# MiscBoard_Switching.net
KiCad netlist of a schematic drawn in Altium Designer
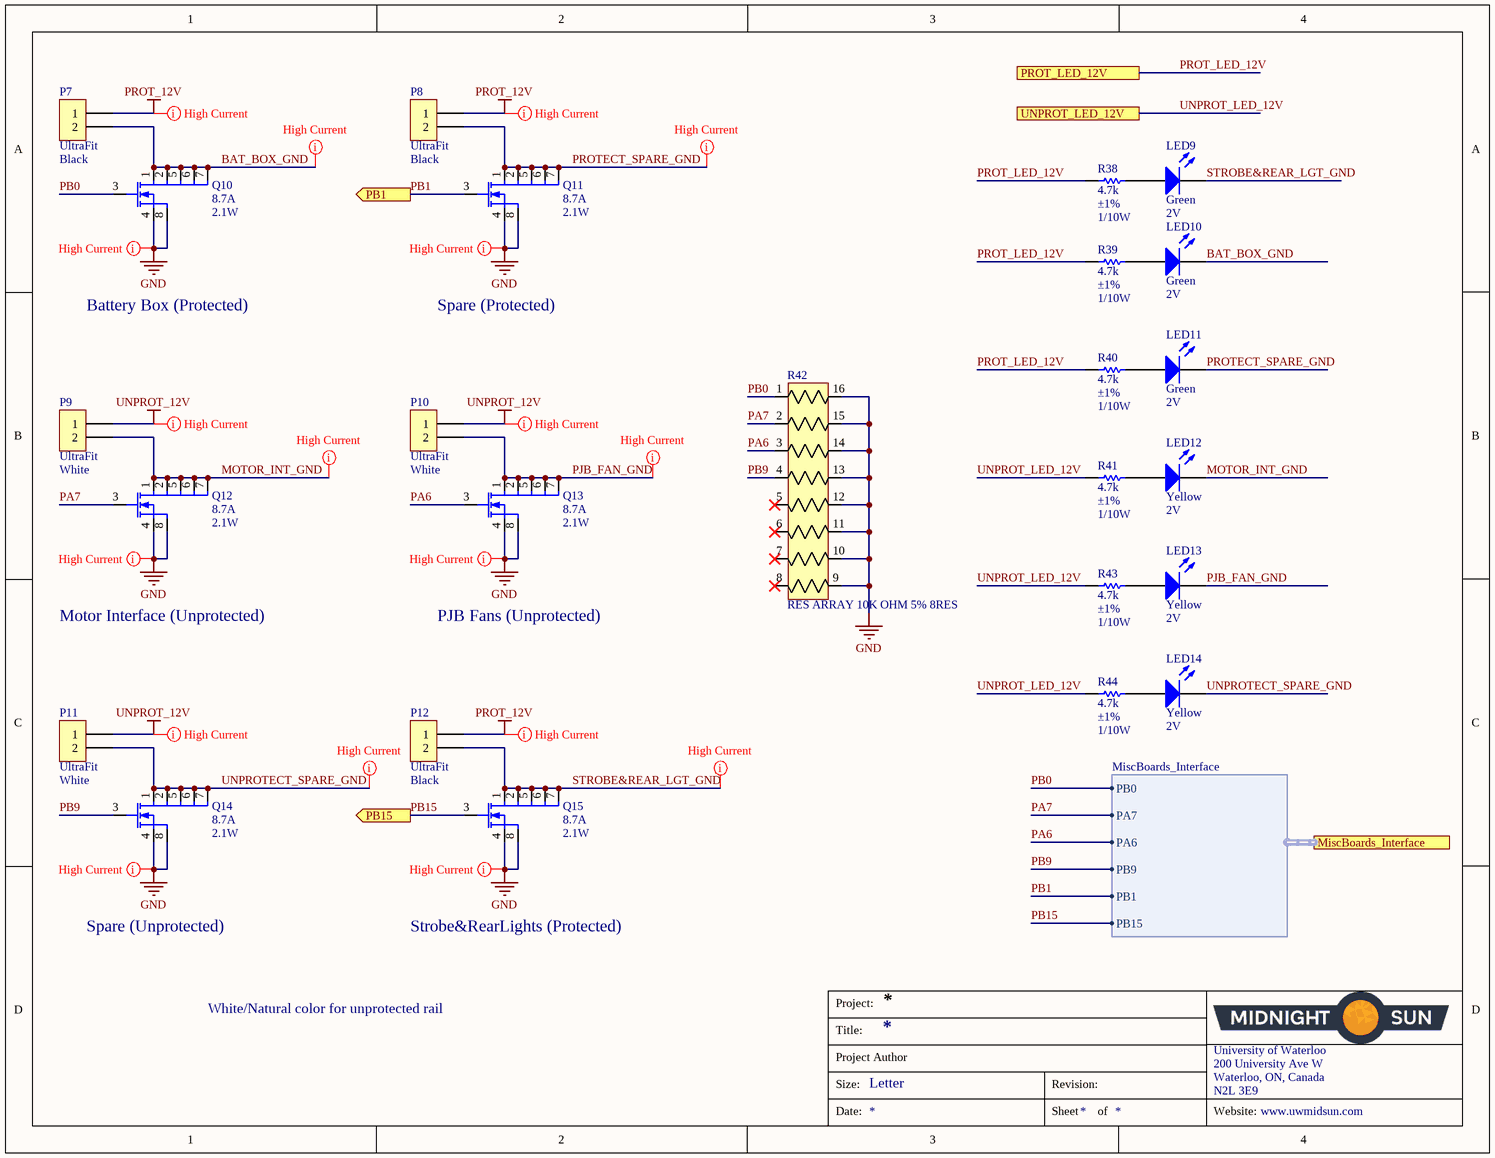
[diagram p0: MiscBoard_Switching.SchDoc]

(export (version "E")
  (design (tool "Eeschema 10.0.6"))
  (components
    (comp (ref "LED9")
      (value "LED GREEN CLEAR 2V 0603")
      (footprint "LED_0603")
      (description "Green 572nm LED Indication - Discrete 2V 0603 (1608 Metric)")
      (fields
        (field (name "COLOR") "Green")
        (field (name "VOLTAGE - FORWARD (VF) (TYP)") "2V")
        (field (name "MANUFACTURER") "Wurth Electronics Inc.")
        (field (name "MANUFACTURER PART NUMBER") "150060VS75000")
      )
      (libsource (lib "Schematic Diagrams") (part "LED GREEN CLEAR 2V 0603"))
    )
    (comp (ref "LED10")
      (value "LED GREEN CLEAR 2V 0603")
      (footprint "LED_0603")
      (description "Green 572nm LED Indication - Discrete 2V 0603 (1608 Metric)")
      (fields
        (field (name "COLOR") "Green")
        (field (name "VOLTAGE - FORWARD (VF) (TYP)") "2V")
        (field (name "MANUFACTURER") "Wurth Electronics Inc.")
        (field (name "MANUFACTURER PART NUMBER") "150060VS75000")
      )
      (libsource (lib "Schematic Diagrams") (part "LED GREEN CLEAR 2V 0603"))
    )
    (comp (ref "LED11")
      (value "LED GREEN CLEAR 2V 0603")
      (footprint "LED_0603")
      (description "Green 572nm LED Indication - Discrete 2V 0603 (1608 Metric)")
      (fields
        (field (name "COLOR") "Green")
        (field (name "VOLTAGE - FORWARD (VF) (TYP)") "2V")
        (field (name "MANUFACTURER") "Wurth Electronics Inc.")
        (field (name "MANUFACTURER PART NUMBER") "150060VS75000")
      )
      (libsource (lib "Schematic Diagrams") (part "LED GREEN CLEAR 2V 0603"))
    )
    (comp (ref "LED12")
      (value "LED YELLOW CLEAR 2.1V 0603")
      (footprint "LED_0603")
      (description "Yellow 590nm LED Indication - Discrete 2V 0603 (1608 Metric)")
      (fields
        (field (name "VOLTAGE - FORWARD (VF) (TYP)") "2V")
        (field (name "MANUFACTURER") "Wurth Electronics Inc.")
        (field (name "MANUFACTURER PART NUMBER") "150060YS75000")
      )
      (libsource (lib "Schematic Diagrams") (part "LED YELLOW CLEAR 2.1V 0603"))
    )
    (comp (ref "LED13")
      (value "LED YELLOW CLEAR 2.1V 0603")
      (footprint "LED_0603")
      (description "Yellow 590nm LED Indication - Discrete 2V 0603 (1608 Metric)")
      (fields
        (field (name "VOLTAGE - FORWARD (VF) (TYP)") "2V")
        (field (name "MANUFACTURER") "Wurth Electronics Inc.")
        (field (name "MANUFACTURER PART NUMBER") "150060YS75000")
      )
      (libsource (lib "Schematic Diagrams") (part "LED YELLOW CLEAR 2.1V 0603"))
    )
    (comp (ref "LED14")
      (value "LED YELLOW CLEAR 2.1V 0603")
      (footprint "LED_0603")
      (description "Yellow 590nm LED Indication - Discrete 2V 0603 (1608 Metric)")
      (fields
        (field (name "VOLTAGE - FORWARD (VF) (TYP)") "2V")
        (field (name "MANUFACTURER") "Wurth Electronics Inc.")
        (field (name "MANUFACTURER PART NUMBER") "150060YS75000")
      )
      (libsource (lib "Schematic Diagrams") (part "LED YELLOW CLEAR 2.1V 0603"))
    )
    (comp (ref "P7")
      (value "CONN 2POS ULTRA-FIT 0.138\"")
      (footprint "CONN, 2POS ULTRA-FIT")
      (description "2 Positions Header, Shrouded Connector 0.138\" (3.50mm) Through Hole Gold")
      (fields
        (field (name "INSULATION COLOR") "Black")
        (field (name "SERIES") "UltraFit")
        (field (name "VOLTAGE") "400V")
      )
      (libsource (lib "Schematic Diagrams") (part "CONN 2POS ULTRA-FIT 0.138{dblquote}"))
    )
    (comp (ref "P8")
      (value "CONN 2POS ULTRA-FIT 0.138\"")
      (footprint "CONN, 2POS ULTRA-FIT")
      (description "2 Positions Header, Shrouded Connector 0.138\" (3.50mm) Through Hole Gold")
      (fields
        (field (name "INSULATION COLOR") "Black")
        (field (name "SERIES") "UltraFit")
        (field (name "VOLTAGE") "400V")
      )
      (libsource (lib "Schematic Diagrams") (part "CONN 2POS ULTRA-FIT 0.138{dblquote}"))
    )
    (comp (ref "P9")
      (value "CONN 2POS ULTRA-FIT NATURAL COLOR 0.138\"")
      (footprint "CONN, 2POS ULTRA-FIT - NATURAL COLOR")
      (description "2 Positions Header, Shrouded Connector 0.138\" (3.50mm) Through Hole")
      (fields
        (field (name "SERIES") "UltraFit")
        (field (name "COLOR") "White")
        (field (name "VOLTAGE") "400V")
      )
      (libsource (lib "Schematic Diagrams") (part "CONN 2POS ULTRA-FIT NATURAL COLOR 0.138{dblquote}"))
    )
    (comp (ref "P10")
      (value "CONN 2POS ULTRA-FIT NATURAL COLOR 0.138\"")
      (footprint "CONN, 2POS ULTRA-FIT - NATURAL COLOR")
      (description "2 Positions Header, Shrouded Connector 0.138\" (3.50mm) Through Hole")
      (fields
        (field (name "SERIES") "UltraFit")
        (field (name "COLOR") "White")
        (field (name "VOLTAGE") "400V")
      )
      (libsource (lib "Schematic Diagrams") (part "CONN 2POS ULTRA-FIT NATURAL COLOR 0.138{dblquote}"))
    )
    (comp (ref "P11")
      (value "CONN 2POS ULTRA-FIT NATURAL COLOR 0.138\"")
      (footprint "CONN, 2POS ULTRA-FIT - NATURAL COLOR")
      (description "2 Positions Header, Shrouded Connector 0.138\" (3.50mm) Through Hole")
      (fields
        (field (name "SERIES") "UltraFit")
        (field (name "COLOR") "White")
        (field (name "VOLTAGE") "400V")
      )
      (libsource (lib "Schematic Diagrams") (part "CONN 2POS ULTRA-FIT NATURAL COLOR 0.138{dblquote}"))
    )
    (comp (ref "P12")
      (value "CONN 2POS ULTRA-FIT 0.138\"")
      (footprint "CONN, 2POS ULTRA-FIT")
      (description "2 Positions Header, Shrouded Connector 0.138\" (3.50mm) Through Hole Gold")
      (fields
        (field (name "INSULATION COLOR") "Black")
        (field (name "SERIES") "UltraFit")
        (field (name "VOLTAGE") "400V")
      )
      (libsource (lib "Schematic Diagrams") (part "CONN 2POS ULTRA-FIT 0.138{dblquote}"))
    )
    (comp (ref "Q10")
      (value "MOSFET N-CH 30V 8.7A 2.1W 6-PQFN (2x2)")
      (footprint "MOSFET N-CH 30V 12A 2mmx2mm PQFN")
      (fields
        (field (name "CURRENT - CONTINUOUS DRAIN (ID) @ 25°C") "8.7A")
        (field (name "POWER DISSIPATION (MAX)") "2.1W")
      )
      (libsource (lib "Schematic Diagrams") (part "MOSFET N-CH 30V 8.7A 2.1W 6-PQFN (2x2)"))
    )
    (comp (ref "Q11")
      (value "MOSFET N-CH 30V 8.7A 2.1W 6-PQFN (2x2)")
      (footprint "MOSFET N-CH 30V 12A 2mmx2mm PQFN")
      (fields
        (field (name "CURRENT - CONTINUOUS DRAIN (ID) @ 25°C") "8.7A")
        (field (name "POWER DISSIPATION (MAX)") "2.1W")
      )
      (libsource (lib "Schematic Diagrams") (part "MOSFET N-CH 30V 8.7A 2.1W 6-PQFN (2x2)"))
    )
    (comp (ref "Q12")
      (value "MOSFET N-CH 30V 8.7A 2.1W 6-PQFN (2x2)")
      (footprint "MOSFET N-CH 30V 12A 2mmx2mm PQFN")
      (fields
        (field (name "CURRENT - CONTINUOUS DRAIN (ID) @ 25°C") "8.7A")
        (field (name "POWER DISSIPATION (MAX)") "2.1W")
      )
      (libsource (lib "Schematic Diagrams") (part "MOSFET N-CH 30V 8.7A 2.1W 6-PQFN (2x2)"))
    )
    (comp (ref "Q13")
      (value "MOSFET N-CH 30V 8.7A 2.1W 6-PQFN (2x2)")
      (footprint "MOSFET N-CH 30V 12A 2mmx2mm PQFN")
      (fields
        (field (name "CURRENT - CONTINUOUS DRAIN (ID) @ 25°C") "8.7A")
        (field (name "POWER DISSIPATION (MAX)") "2.1W")
      )
      (libsource (lib "Schematic Diagrams") (part "MOSFET N-CH 30V 8.7A 2.1W 6-PQFN (2x2)"))
    )
    (comp (ref "Q14")
      (value "MOSFET N-CH 30V 8.7A 2.1W 6-PQFN (2x2)")
      (footprint "MOSFET N-CH 30V 12A 2mmx2mm PQFN")
      (fields
        (field (name "CURRENT - CONTINUOUS DRAIN (ID) @ 25°C") "8.7A")
        (field (name "POWER DISSIPATION (MAX)") "2.1W")
      )
      (libsource (lib "Schematic Diagrams") (part "MOSFET N-CH 30V 8.7A 2.1W 6-PQFN (2x2)"))
    )
    (comp (ref "Q15")
      (value "MOSFET N-CH 30V 8.7A 2.1W 6-PQFN (2x2)")
      (footprint "MOSFET N-CH 30V 12A 2mmx2mm PQFN")
      (fields
        (field (name "CURRENT - CONTINUOUS DRAIN (ID) @ 25°C") "8.7A")
        (field (name "POWER DISSIPATION (MAX)") "2.1W")
      )
      (libsource (lib "Schematic Diagrams") (part "MOSFET N-CH 30V 8.7A 2.1W 6-PQFN (2x2)"))
    )
    (comp (ref "R38")
      (value "RES 4.7K OHM 1% 1/10W 0603")
      (footprint "RES, 0603")
      (description "4.7k Ohm ±1% 0.1W, 1/10W Chip Resistor 0603 (1608 Metric) Moisture Resistant Thick Film")
      (fields
        (field (name "RESISTANCE (OHMS)") "4.7k")
        (field (name "TOLERANCE") "±1%")
        (field (name "POWER (WATTS)") "1/10W")
      )
      (libsource (lib "Schematic Diagrams") (part "RES 4.7K OHM 1% 1/10W 0603"))
    )
    (comp (ref "R39")
      (value "RES 4.7K OHM 1% 1/10W 0603")
      (footprint "RES, 0603")
      (description "4.7k Ohm ±1% 0.1W, 1/10W Chip Resistor 0603 (1608 Metric) Moisture Resistant Thick Film")
      (fields
        (field (name "RESISTANCE (OHMS)") "4.7k")
        (field (name "TOLERANCE") "±1%")
        (field (name "POWER (WATTS)") "1/10W")
      )
      (libsource (lib "Schematic Diagrams") (part "RES 4.7K OHM 1% 1/10W 0603"))
    )
    (comp (ref "R40")
      (value "RES 4.7K OHM 1% 1/10W 0603")
      (footprint "RES, 0603")
      (description "4.7k Ohm ±1% 0.1W, 1/10W Chip Resistor 0603 (1608 Metric) Moisture Resistant Thick Film")
      (fields
        (field (name "RESISTANCE (OHMS)") "4.7k")
        (field (name "TOLERANCE") "±1%")
        (field (name "POWER (WATTS)") "1/10W")
      )
      (libsource (lib "Schematic Diagrams") (part "RES 4.7K OHM 1% 1/10W 0603"))
    )
    (comp (ref "R41")
      (value "RES 4.7K OHM 1% 1/10W 0603")
      (footprint "RES, 0603")
      (description "4.7k Ohm ±1% 0.1W, 1/10W Chip Resistor 0603 (1608 Metric) Moisture Resistant Thick Film")
      (fields
        (field (name "RESISTANCE (OHMS)") "4.7k")
        (field (name "TOLERANCE") "±1%")
        (field (name "POWER (WATTS)") "1/10W")
      )
      (libsource (lib "Schematic Diagrams") (part "RES 4.7K OHM 1% 1/10W 0603"))
    )
    (comp (ref "R42")
      (value "RES ARRAY 10K OHM 5% 8RES")
      (footprint "RES ARRAY, 8 POS 1506")
      (description "RES ARRAY SMD 10K 5% 62.5mW 1506")
      (fields
        (field (name "MANUFACTURER_PART_NUMBER") "EXB-2HV103JV")
        (field (name "MANUFACTURER") "Panasonic Electronic Components")
        (field (name "COPYRIGHT") "Copyright (C) 2015 Accelerated Designs. All rights reserved")
      )
      (libsource (lib "Schematic Diagrams") (part "RES ARRAY 10K OHM 5% 8RES EXB-2HV103JV"))
    )
    (comp (ref "R43")
      (value "RES 4.7K OHM 1% 1/10W 0603")
      (footprint "RES, 0603")
      (description "4.7k Ohm ±1% 0.1W, 1/10W Chip Resistor 0603 (1608 Metric) Moisture Resistant Thick Film")
      (fields
        (field (name "RESISTANCE (OHMS)") "4.7k")
        (field (name "TOLERANCE") "±1%")
        (field (name "POWER (WATTS)") "1/10W")
      )
      (libsource (lib "Schematic Diagrams") (part "RES 4.7K OHM 1% 1/10W 0603"))
    )
    (comp (ref "R44")
      (value "RES 4.7K OHM 1% 1/10W 0603")
      (footprint "RES, 0603")
      (description "4.7k Ohm ±1% 0.1W, 1/10W Chip Resistor 0603 (1608 Metric) Moisture Resistant Thick Film")
      (fields
        (field (name "RESISTANCE (OHMS)") "4.7k")
        (field (name "TOLERANCE") "±1%")
        (field (name "POWER (WATTS)") "1/10W")
      )
      (libsource (lib "Schematic Diagrams") (part "RES 4.7K OHM 1% 1/10W 0603"))
    )
  )
  (nets
    (net (code "2") (name "/BAT_BOX_GND") (class "Default")
      (node (ref "LED10") (pin "2") (pinfunction "K_2") (pintype "passive"))
      (node (ref "P7") (pin "2") (pinfunction "2_2") (pintype "passive"))
      (node (ref "Q10") (pin "1") (pinfunction "D_1") (pintype "passive"))
      (node (ref "Q10") (pin "2") (pinfunction "D_2") (pintype "passive"))
      (node (ref "Q10") (pin "5") (pinfunction "D_5") (pintype "passive"))
      (node (ref "Q10") (pin "6") (pinfunction "D_6") (pintype "passive"))
      (node (ref "Q10") (pin "7") (pinfunction "D_7") (pintype "passive"))
    )
    (net (code "3") (name "/MOTOR_INT_GND") (class "Default")
      (node (ref "LED12") (pin "2") (pinfunction "K_2") (pintype "passive"))
      (node (ref "P9") (pin "2") (pinfunction "2_2") (pintype "passive"))
      (node (ref "Q12") (pin "1") (pinfunction "D_1") (pintype "passive"))
      (node (ref "Q12") (pin "2") (pinfunction "D_2") (pintype "passive"))
      (node (ref "Q12") (pin "5") (pinfunction "D_5") (pintype "passive"))
      (node (ref "Q12") (pin "6") (pinfunction "D_6") (pintype "passive"))
      (node (ref "Q12") (pin "7") (pinfunction "D_7") (pintype "passive"))
    )
    (net (code "4") (name "/PA6") (class "Default")
      (node (ref "Q13") (pin "3") (pinfunction "G_3") (pintype "passive"))
      (node (ref "R42") (pin "3") (pinfunction "3_3") (pintype "passive"))
    )
    (net (code "5") (name "/PA7") (class "Default")
      (node (ref "Q12") (pin "3") (pinfunction "G_3") (pintype "passive"))
      (node (ref "R42") (pin "2") (pinfunction "2_2") (pintype "passive"))
    )
    (net (code "6") (name "/PB0") (class "Default")
      (node (ref "Q10") (pin "3") (pinfunction "G_3") (pintype "passive"))
      (node (ref "R42") (pin "1") (pinfunction "1_1") (pintype "passive"))
    )
    (net (code "7") (name "/PB1") (class "Default")
      (node (ref "Q11") (pin "3") (pinfunction "G_3") (pintype "passive"))
    )
    (net (code "8") (name "/PB9") (class "Default")
      (node (ref "Q14") (pin "3") (pinfunction "G_3") (pintype "passive"))
      (node (ref "R42") (pin "4") (pinfunction "4_4") (pintype "passive"))
    )
    (net (code "9") (name "/PB15") (class "Default")
      (node (ref "Q15") (pin "3") (pinfunction "G_3") (pintype "passive"))
    )
    (net (code "10") (name "/PJB_FAN_GND") (class "Default")
      (node (ref "LED13") (pin "2") (pinfunction "K_2") (pintype "passive"))
      (node (ref "P10") (pin "2") (pinfunction "2_2") (pintype "passive"))
      (node (ref "Q13") (pin "1") (pinfunction "D_1") (pintype "passive"))
      (node (ref "Q13") (pin "2") (pinfunction "D_2") (pintype "passive"))
      (node (ref "Q13") (pin "5") (pinfunction "D_5") (pintype "passive"))
      (node (ref "Q13") (pin "6") (pinfunction "D_6") (pintype "passive"))
      (node (ref "Q13") (pin "7") (pinfunction "D_7") (pintype "passive"))
    )
    (net (code "11") (name "/PROTECT_SPARE_GND") (class "Default")
      (node (ref "LED11") (pin "2") (pinfunction "K_2") (pintype "passive"))
      (node (ref "P8") (pin "2") (pinfunction "2_2") (pintype "passive"))
      (node (ref "Q11") (pin "1") (pinfunction "D_1") (pintype "passive"))
      (node (ref "Q11") (pin "2") (pinfunction "D_2") (pintype "passive"))
      (node (ref "Q11") (pin "5") (pinfunction "D_5") (pintype "passive"))
      (node (ref "Q11") (pin "6") (pinfunction "D_6") (pintype "passive"))
      (node (ref "Q11") (pin "7") (pinfunction "D_7") (pintype "passive"))
    )
    (net (code "12") (name "/PROT_LED_12V") (class "Default")
      (node (ref "R38") (pin "1") (pinfunction "1_1") (pintype "passive"))
      (node (ref "R39") (pin "1") (pinfunction "1_1") (pintype "passive"))
      (node (ref "R40") (pin "1") (pinfunction "1_1") (pintype "passive"))
    )
    (net (code "13") (name "/STROBE&REAR_LGT_GND") (class "Default")
      (node (ref "LED9") (pin "2") (pinfunction "K_2") (pintype "passive"))
      (node (ref "P12") (pin "2") (pinfunction "2_2") (pintype "passive"))
      (node (ref "Q15") (pin "1") (pinfunction "D_1") (pintype "passive"))
      (node (ref "Q15") (pin "2") (pinfunction "D_2") (pintype "passive"))
      (node (ref "Q15") (pin "5") (pinfunction "D_5") (pintype "passive"))
      (node (ref "Q15") (pin "6") (pinfunction "D_6") (pintype "passive"))
      (node (ref "Q15") (pin "7") (pinfunction "D_7") (pintype "passive"))
    )
    (net (code "14") (name "/UNPROTECT_SPARE_GND") (class "Default")
      (node (ref "LED14") (pin "2") (pinfunction "K_2") (pintype "passive"))
      (node (ref "P11") (pin "2") (pinfunction "2_2") (pintype "passive"))
      (node (ref "Q14") (pin "1") (pinfunction "D_1") (pintype "passive"))
      (node (ref "Q14") (pin "2") (pinfunction "D_2") (pintype "passive"))
      (node (ref "Q14") (pin "5") (pinfunction "D_5") (pintype "passive"))
      (node (ref "Q14") (pin "6") (pinfunction "D_6") (pintype "passive"))
      (node (ref "Q14") (pin "7") (pinfunction "D_7") (pintype "passive"))
    )
    (net (code "15") (name "/UNPROT_LED_12V") (class "Default")
      (node (ref "R41") (pin "1") (pinfunction "1_1") (pintype "passive"))
      (node (ref "R43") (pin "1") (pinfunction "1_1") (pintype "passive"))
      (node (ref "R44") (pin "1") (pinfunction "1_1") (pintype "passive"))
    )
    (net (code "17") (name "GND") (class "Default")
      (node (ref "Q10") (pin "4") (pinfunction "S_4") (pintype "passive"))
      (node (ref "Q10") (pin "8") (pinfunction "S_8") (pintype "passive"))
      (node (ref "Q11") (pin "4") (pinfunction "S_4") (pintype "passive"))
      (node (ref "Q11") (pin "8") (pinfunction "S_8") (pintype "passive"))
      (node (ref "Q12") (pin "4") (pinfunction "S_4") (pintype "passive"))
      (node (ref "Q12") (pin "8") (pinfunction "S_8") (pintype "passive"))
      (node (ref "Q13") (pin "4") (pinfunction "S_4") (pintype "passive"))
      (node (ref "Q13") (pin "8") (pinfunction "S_8") (pintype "passive"))
      (node (ref "Q14") (pin "4") (pinfunction "S_4") (pintype "passive"))
      (node (ref "Q14") (pin "8") (pinfunction "S_8") (pintype "passive"))
      (node (ref "Q15") (pin "4") (pinfunction "S_4") (pintype "passive"))
      (node (ref "Q15") (pin "8") (pinfunction "S_8") (pintype "passive"))
      (node (ref "R42") (pin "10") (pinfunction "10_10") (pintype "passive"))
      (node (ref "R42") (pin "11") (pinfunction "11_11") (pintype "passive"))
      (node (ref "R42") (pin "12") (pinfunction "12_12") (pintype "passive"))
      (node (ref "R42") (pin "13") (pinfunction "13_13") (pintype "passive"))
      (node (ref "R42") (pin "14") (pinfunction "14_14") (pintype "passive"))
      (node (ref "R42") (pin "15") (pinfunction "15_15") (pintype "passive"))
      (node (ref "R42") (pin "16") (pinfunction "16_16") (pintype "passive"))
      (node (ref "R42") (pin "9") (pinfunction "9_9") (pintype "passive"))
    )
    (net (code "18") (name "Net-(LED9-A)") (class "Default")
      (node (ref "LED9") (pin "1") (pinfunction "A_1") (pintype "passive"))
      (node (ref "R38") (pin "2") (pinfunction "2_2") (pintype "passive"))
    )
    (net (code "19") (name "Net-(LED10-A)") (class "Default")
      (node (ref "LED10") (pin "1") (pinfunction "A_1") (pintype "passive"))
      (node (ref "R39") (pin "2") (pinfunction "2_2") (pintype "passive"))
    )
    (net (code "20") (name "Net-(LED11-A)") (class "Default")
      (node (ref "LED11") (pin "1") (pinfunction "A_1") (pintype "passive"))
      (node (ref "R40") (pin "2") (pinfunction "2_2") (pintype "passive"))
    )
    (net (code "21") (name "Net-(LED12-A)") (class "Default")
      (node (ref "LED12") (pin "1") (pinfunction "A_1") (pintype "passive"))
      (node (ref "R41") (pin "2") (pinfunction "2_2") (pintype "passive"))
    )
    (net (code "22") (name "Net-(LED13-A)") (class "Default")
      (node (ref "LED13") (pin "1") (pinfunction "A_1") (pintype "passive"))
      (node (ref "R43") (pin "2") (pinfunction "2_2") (pintype "passive"))
    )
    (net (code "23") (name "Net-(LED14-A)") (class "Default")
      (node (ref "LED14") (pin "1") (pinfunction "A_1") (pintype "passive"))
      (node (ref "R44") (pin "2") (pinfunction "2_2") (pintype "passive"))
    )
    (net (code "24") (name "PROT_12V") (class "Default")
      (node (ref "P12") (pin "1") (pinfunction "1_1") (pintype "passive"))
      (node (ref "P7") (pin "1") (pinfunction "1_1") (pintype "passive"))
      (node (ref "P8") (pin "1") (pinfunction "1_1") (pintype "passive"))
    )
    (net (code "25") (name "UNPROT_12V") (class "Default")
      (node (ref "P10") (pin "1") (pinfunction "1_1") (pintype "passive"))
      (node (ref "P11") (pin "1") (pinfunction "1_1") (pintype "passive"))
      (node (ref "P9") (pin "1") (pinfunction "1_1") (pintype "passive"))
    )
    (net (code "26") (name "unconnected-(R42-Pad5)") (class "Default")
      (node (ref "R42") (pin "5") (pinfunction "5_5") (pintype "passive+no_connect"))
    )
    (net (code "27") (name "unconnected-(R42-Pad6)") (class "Default")
      (node (ref "R42") (pin "6") (pinfunction "6_6") (pintype "passive+no_connect"))
    )
    (net (code "28") (name "unconnected-(R42-Pad7)") (class "Default")
      (node (ref "R42") (pin "7") (pinfunction "7_7") (pintype "passive+no_connect"))
    )
    (net (code "29") (name "unconnected-(R42-Pad8)") (class "Default")
      (node (ref "R42") (pin "8") (pinfunction "8_8") (pintype "passive+no_connect"))
    )
  )
)
